# CANBed_case.net
KiCad netlist of a schematic drawn in EAGLE
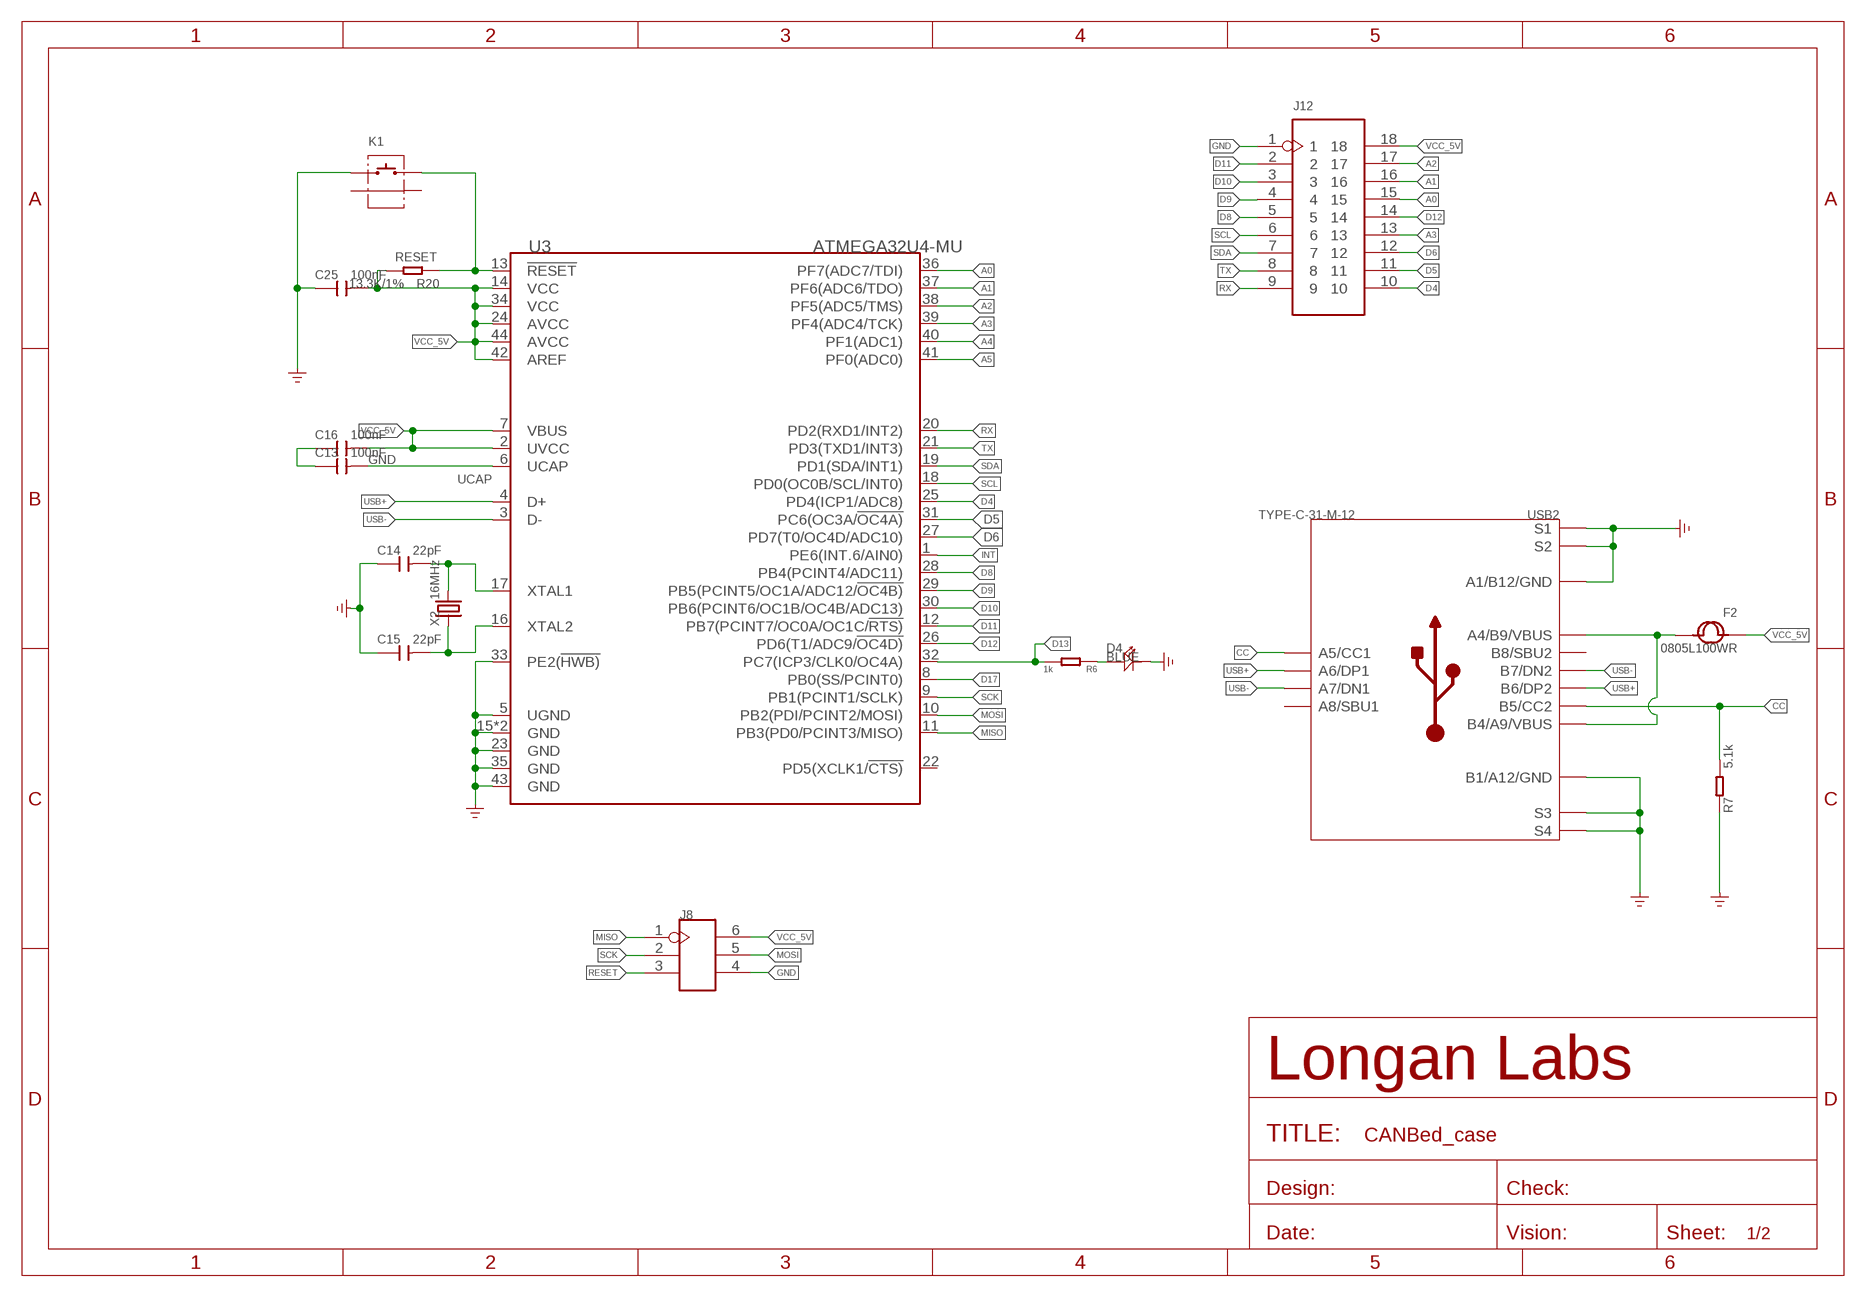
[diagram p0: schematic, sheet 1, part 1 of 2]
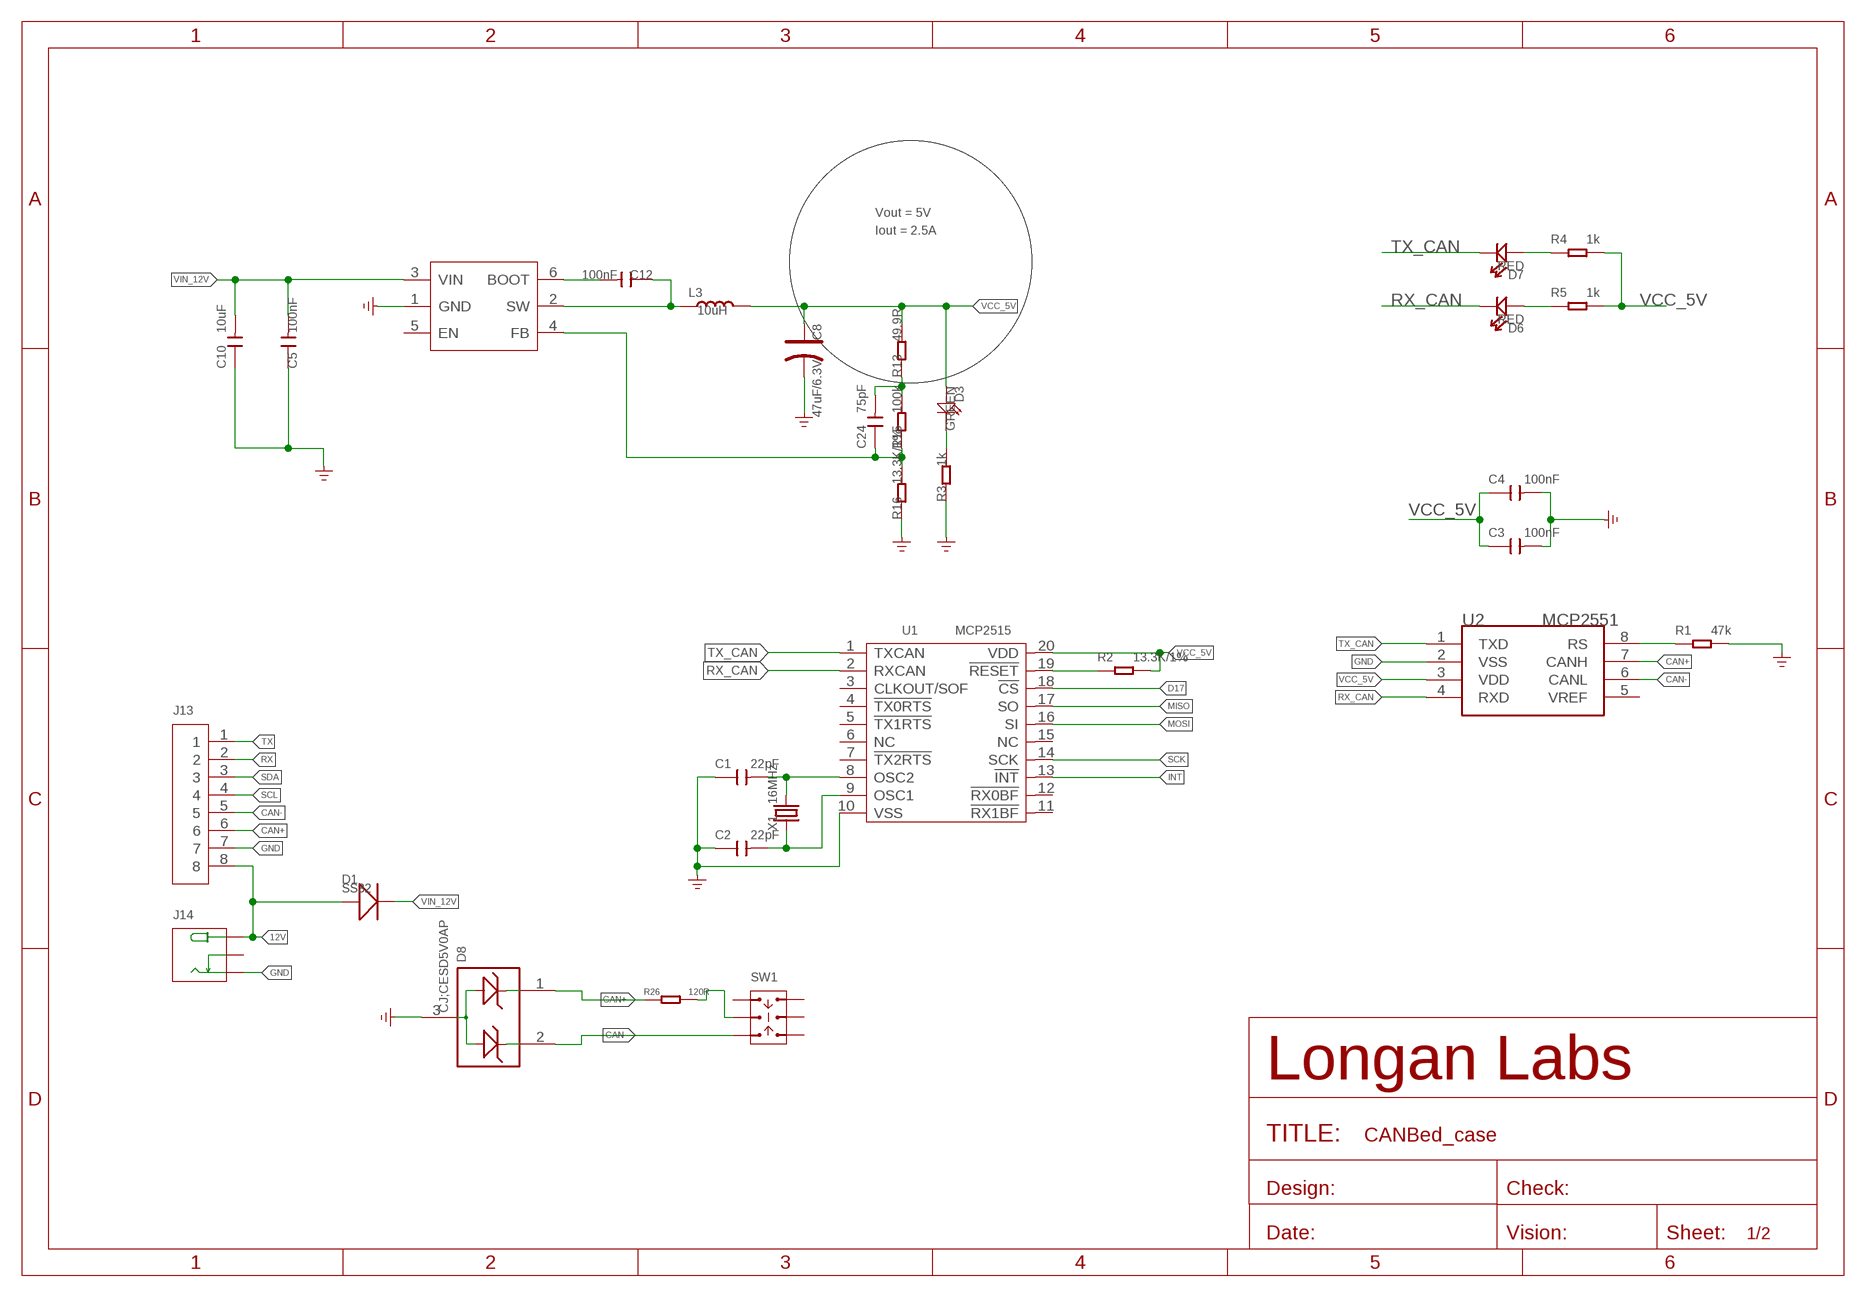
[diagram p1: schematic, sheet 1, part 2 of 2]

(export (version "E")
  (design (tool "Eeschema 10.0.6"))
  (components
    (comp (ref "C1")
      (value "22pF")
      (footprint "eagle-import:C0603")
      (libsource (lib "eagle-import") (part "CAP-0603"))
    )
    (comp (ref "C2")
      (value "22pF")
      (footprint "eagle-import:C0603")
      (libsource (lib "eagle-import") (part "CAP-0603"))
    )
    (comp (ref "C3")
      (value "100nF")
      (footprint "eagle-import:C0603")
      (libsource (lib "eagle-import") (part "CAP-0603"))
    )
    (comp (ref "C4")
      (value "100nF")
      (footprint "eagle-import:C0603")
      (libsource (lib "eagle-import") (part "CAP-0603"))
    )
    (comp (ref "C5")
      (value "100nF")
      (footprint "eagle-import:C0603")
      (libsource (lib "eagle-import") (part "CAP-0603"))
    )
    (comp (ref "C8")
      (value "47uF/6.3V")
      (footprint "eagle-import:AVX-B")
      (libsource (lib "eagle-import") (part "CAP-POLAR-AVX-B"))
    )
    (comp (ref "C10")
      (value "10uF")
      (footprint "eagle-import:C1206")
      (libsource (lib "eagle-import") (part "CAP-1206"))
    )
    (comp (ref "C12")
      (value "100nF")
      (footprint "eagle-import:C0603")
      (libsource (lib "eagle-import") (part "CAP-0603"))
    )
    (comp (ref "C13")
      (value "100nF")
      (footprint "eagle-import:C0603")
      (libsource (lib "eagle-import") (part "CAP-0603"))
    )
    (comp (ref "C14")
      (value "22pF")
      (footprint "eagle-import:C0603")
      (libsource (lib "eagle-import") (part "CAP-0603"))
    )
    (comp (ref "C15")
      (value "22pF")
      (footprint "eagle-import:C0603")
      (libsource (lib "eagle-import") (part "CAP-0603"))
    )
    (comp (ref "C16")
      (value "100nF")
      (footprint "eagle-import:C0603")
      (libsource (lib "eagle-import") (part "CAP-0603"))
    )
    (comp (ref "C24")
      (value "75pF")
      (footprint "eagle-import:C0603")
      (libsource (lib "eagle-import") (part "CAP-0603"))
    )
    (comp (ref "C25")
      (value "100nF")
      (footprint "eagle-import:C0603")
      (libsource (lib "eagle-import") (part "CAP-0603"))
    )
    (comp (ref "D1")
      (value "SS32")
      (footprint "eagle-import:DO-214AC")
      (libsource (lib "eagle-import") (part "DIODE'SMA'"))
    )
    (comp (ref "D3")
      (value "GREEN")
      (footprint "eagle-import:LED0805-SIDE")
      (libsource (lib "eagle-import") (part "fat cong_LED'0805'"))
    )
    (comp (ref "D4")
      (value "BLUE")
      (footprint "eagle-import:LED0805-SIDE")
      (libsource (lib "eagle-import") (part "fat cong_LED'0805'"))
    )
    (comp (ref "D6")
      (value "RED")
      (footprint "eagle-import:LED-0603")
      (libsource (lib "eagle-import") (part "LED'0603'"))
    )
    (comp (ref "D7")
      (value "RED")
      (footprint "eagle-import:LED-0603")
      (libsource (lib "eagle-import") (part "LED'0603'"))
    )
    (comp (ref "D8")
      (value "CJ;CESD5V0AP")
      (footprint "eagle-import:SOT-23")
      (libsource (lib "eagle-import") (part "D-ESD-3P'CESD3V3AP'"))
    )
    (comp (ref "F2")
      (value "0805L100WR")
      (footprint "eagle-import:F0805")
      (libsource (lib "eagle-import") (part "FUSE0805"))
    )
    (comp (ref "J8")
      (value "HEADER-2X3P-2.54")
      (footprint "eagle-import:H2X3-2.54")
      (libsource (lib "eagle-import") (part "HEADER-2X3P-2.54"))
    )
    (comp (ref "J12")
      (value "HEADER-2X9P-2.54")
      (footprint "eagle-import:H2X9-2.54")
      (libsource (lib "eagle-import") (part "HEADER-2X9P-2.54"))
    )
    (comp (ref "J13")
      (value "TERMINAL-8P")
      (footprint "eagle-import:TERMINAL8P-5.0-41.2X12.2X7.8MM")
      (libsource (lib "eagle-import") (part "TERMINAL-8P"))
    )
    (comp (ref "J14")
      (value "POWER-JACK-DC-320120003")
      (footprint "eagle-import:DCJ3P-14.2X11.0X9.0MM")
      (libsource (lib "eagle-import") (part "POWER-JACK-DC-320120003"))
    )
    (comp (ref "K1")
      (value "BUTTON-2+2P-K2-1102AQ")
      (footprint "eagle-import:SW4-4.5-7X6.8X6MM")
      (libsource (lib "eagle-import") (part "BUTTON-2+2P-K2-1102AQ"))
    )
    (comp (ref "L3")
      (value "10uH")
      (footprint "eagle-import:INT2-SMD-6.6X7.1X3MM")
      (libsource (lib "eagle-import") (part "INDUCTOR-6.6X7.1"))
    )
    (comp (ref "R1")
      (value "47k")
      (footprint "eagle-import:R0603")
      (libsource (lib "eagle-import") (part "RES-0603"))
    )
    (comp (ref "R2")
      (value "13.3K/1%")
      (footprint "eagle-import:R0603")
      (libsource (lib "eagle-import") (part "RES-0603"))
    )
    (comp (ref "R3")
      (value "1k")
      (footprint "eagle-import:R0603")
      (libsource (lib "eagle-import") (part "RES-0603"))
    )
    (comp (ref "R4")
      (value "1k")
      (footprint "eagle-import:R0603")
      (libsource (lib "eagle-import") (part "RES-0603"))
    )
    (comp (ref "R5")
      (value "1k")
      (footprint "eagle-import:R0603")
      (libsource (lib "eagle-import") (part "RES-0603"))
    )
    (comp (ref "R6")
      (value "1k")
      (footprint "eagle-import:R0603")
      (libsource (lib "eagle-import") (part "RES-0603"))
    )
    (comp (ref "R7")
      (value "5.1k")
      (footprint "eagle-import:R0603")
      (libsource (lib "eagle-import") (part "RES-0603"))
    )
    (comp (ref "R13")
      (value "49.9R")
      (footprint "eagle-import:R0603")
      (libsource (lib "eagle-import") (part "RES-0603"))
    )
    (comp (ref "R15")
      (value "100k")
      (footprint "eagle-import:R0603")
      (libsource (lib "eagle-import") (part "RES-0603"))
    )
    (comp (ref "R16")
      (value "13.3K/1%")
      (footprint "eagle-import:R0603")
      (libsource (lib "eagle-import") (part "RES-0603"))
    )
    (comp (ref "R20")
      (value "13.3K/1%")
      (footprint "eagle-import:R0603")
      (libsource (lib "eagle-import") (part "RES-0603"))
    )
    (comp (ref "R26")
      (value "120R")
      (footprint "eagle-import:R0603")
      (libsource (lib "eagle-import") (part "RES-0603"))
    )
    (comp (ref "SW1")
      (value "SWITCH-2CH-6P-311010004")
      (footprint "eagle-import:SW6-2.54-9.0X3.5X3.2+2.0MM")
      (libsource (lib "eagle-import") (part "SWITCH-2CH-6P-311010004"))
    )
    (comp (ref "U1")
      (value "MCP2515")
      (footprint "eagle-import:TSSOP20-0.65-6.5X4.4MM")
      (libsource (lib "eagle-import") (part "MCP2515'ST'"))
    )
    (comp (ref "U2")
      (value "MCP2551")
      (footprint "eagle-import:SOIC8-6.0")
      (libsource (lib "eagle-import") (part "MCP2551-SOIC8"))
    )
    (comp (ref "U3")
      (value "ATMEGA32U4-MU")
      (footprint "eagle-import:QFN44G-0.5-7X7MM")
      (libsource (lib "eagle-import") (part "MCU-ATMEGA32U4-MUR"))
    )
    (comp (ref "U6")
      (value "PMIC-TPS54302")
      (footprint "eagle-import:SOT-23-6")
      (libsource (lib "eagle-import") (part "PMIC-TPS54302"))
    )
    (comp (ref "USB2")
      (value "TYPE-C-31-M-12")
      (footprint "eagle-import:USB2.0-TYPE-C")
      (libsource (lib "eagle-import") (part "USB2.0-TYPE-C"))
    )
    (comp (ref "X1")
      (value "16MHz")
      (footprint "eagle-import:X4-SMD-3.2X2.5X0.7MM")
      (libsource (lib "eagle-import") (part "CRYSTAL-2P-3225"))
    )
    (comp (ref "X2")
      (value "16MHz")
      (footprint "eagle-import:X4-SMD-3.2X2.5X0.7MM")
      (libsource (lib "eagle-import") (part "CRYSTAL-2P-3225"))
    )
  )
  (nets
    (net (code "1") (name "12V") (class "Default")
      (node (ref "D1") (pin "1") (pinfunction "+_1") (pintype "passive"))
      (node (ref "J13") (pin "8") (pinfunction "8_8") (pintype "bidirectional"))
      (node (ref "J14") (pin "+") (pinfunction "+_+") (pintype "bidirectional"))
    )
    (net (code "2") (name "A0") (class "Default")
      (node (ref "J12") (pin "15") (pinfunction "15_15") (pintype "bidirectional"))
      (node (ref "U3") (pin "36") (pinfunction "PF7(ADC7/TDI)_36") (pintype "bidirectional"))
    )
    (net (code "3") (name "A1") (class "Default")
      (node (ref "J12") (pin "16") (pinfunction "16_16") (pintype "bidirectional"))
      (node (ref "U3") (pin "37") (pinfunction "PF6(ADC6/TDO)_37") (pintype "bidirectional"))
    )
    (net (code "4") (name "A2") (class "Default")
      (node (ref "J12") (pin "17") (pinfunction "17_17") (pintype "bidirectional"))
      (node (ref "U3") (pin "38") (pinfunction "PF5(ADC5/TMS)_38") (pintype "bidirectional"))
    )
    (net (code "5") (name "A3") (class "Default")
      (node (ref "J12") (pin "13") (pinfunction "13_13") (pintype "bidirectional"))
      (node (ref "U3") (pin "39") (pinfunction "PF4(ADC4/TCK)_39") (pintype "bidirectional"))
    )
    (net (code "6") (name "A4") (class "Default")
      (node (ref "U3") (pin "40") (pinfunction "PF1(ADC1)_40") (pintype "bidirectional"))
    )
    (net (code "7") (name "A5") (class "Default")
      (node (ref "U3") (pin "41") (pinfunction "PF0(ADC0)_41") (pintype "bidirectional"))
    )
    (net (code "8") (name "CAN+") (class "Default")
      (node (ref "D8") (pin "1") (pinfunction "1_1") (pintype "bidirectional"))
      (node (ref "J13") (pin "6") (pinfunction "6_6") (pintype "bidirectional"))
      (node (ref "R26") (pin "1") (pinfunction "1_1") (pintype "passive"))
      (node (ref "U2") (pin "7") (pinfunction "CANH_7") (pintype "bidirectional"))
    )
    (net (code "9") (name "CAN-") (class "Default")
      (node (ref "D8") (pin "2") (pinfunction "2_2") (pintype "bidirectional"))
      (node (ref "J13") (pin "5") (pinfunction "5_5") (pintype "bidirectional"))
      (node (ref "SW1") (pin "CH1B") (pinfunction "CH1B_CH1B") (pintype "bidirectional"))
      (node (ref "U2") (pin "6") (pinfunction "CANL_6") (pintype "bidirectional"))
    )
    (net (code "10") (name "CC") (class "Default")
      (node (ref "R7") (pin "2") (pinfunction "2_2") (pintype "passive"))
      (node (ref "USB2") (pin "A5") (pinfunction "A5/CC1_A5") (pintype "bidirectional"))
      (node (ref "USB2") (pin "B5") (pinfunction "B5/CC2_B5") (pintype "bidirectional"))
    )
    (net (code "11") (name "D4") (class "Default")
      (node (ref "J12") (pin "10") (pinfunction "10_10") (pintype "bidirectional"))
      (node (ref "U3") (pin "25") (pinfunction "PD4(ICP1/ADC8)_25") (pintype "bidirectional"))
    )
    (net (code "12") (name "D5") (class "Default")
      (node (ref "J12") (pin "11") (pinfunction "11_11") (pintype "bidirectional"))
      (node (ref "U3") (pin "31") (pinfunction "PC6(OC3A/~{OC4A})_31") (pintype "bidirectional"))
    )
    (net (code "13") (name "D6") (class "Default")
      (node (ref "J12") (pin "12") (pinfunction "12_12") (pintype "bidirectional"))
      (node (ref "U3") (pin "27") (pinfunction "PD7(T0/OC4D/ADC10)_27") (pintype "bidirectional"))
    )
    (net (code "14") (name "D8") (class "Default")
      (node (ref "J12") (pin "5") (pinfunction "5_5") (pintype "bidirectional"))
      (node (ref "U3") (pin "28") (pinfunction "PB4(PCINT4/ADC11)_28") (pintype "bidirectional"))
    )
    (net (code "15") (name "D9") (class "Default")
      (node (ref "J12") (pin "4") (pinfunction "4_4") (pintype "bidirectional"))
      (node (ref "U3") (pin "29") (pinfunction "PB5(PCINT5/OC1A/ADC12/~{OC4B})_29") (pintype "bidirectional"))
    )
    (net (code "16") (name "D10") (class "Default")
      (node (ref "J12") (pin "3") (pinfunction "3_3") (pintype "bidirectional"))
      (node (ref "U3") (pin "30") (pinfunction "PB6(PCINT6/OC1B/OC4B/ADC13)_30") (pintype "bidirectional"))
    )
    (net (code "17") (name "D11") (class "Default")
      (node (ref "J12") (pin "2") (pinfunction "2_2") (pintype "bidirectional"))
      (node (ref "U3") (pin "12") (pinfunction "PB7(PCINT7/OC0A/OC1C/~{RTS})_12") (pintype "bidirectional"))
    )
    (net (code "18") (name "D12") (class "Default")
      (node (ref "J12") (pin "14") (pinfunction "14_14") (pintype "bidirectional"))
      (node (ref "U3") (pin "26") (pinfunction "PD6(T1/ADC9/~{OC4D})_26") (pintype "bidirectional"))
    )
    (net (code "19") (name "D13") (class "Default")
      (node (ref "R6") (pin "2") (pinfunction "2_2") (pintype "passive"))
      (node (ref "U3") (pin "32") (pinfunction "PC7(ICP3/CLK0/OC4A)_32") (pintype "bidirectional"))
    )
    (net (code "20") (name "D17") (class "Default")
      (node (ref "U1") (pin "18") (pinfunction "~{CS}_18") (pintype "bidirectional"))
      (node (ref "U3") (pin "8") (pinfunction "PB0(SS/PCINT0)_8") (pintype "bidirectional"))
    )
    (net (code "21") (name "GND") (class "Default")
      (node (ref "C1") (pin "1") (pinfunction "1_1") (pintype "passive"))
      (node (ref "C10") (pin "1") (pinfunction "1_1") (pintype "passive"))
      (node (ref "C13") (pin "1") (pinfunction "1_1") (pintype "passive"))
      (node (ref "C14") (pin "1") (pinfunction "1_1") (pintype "passive"))
      (node (ref "C15") (pin "1") (pinfunction "1_1") (pintype "passive"))
      (node (ref "C16") (pin "1") (pinfunction "1_1") (pintype "passive"))
      (node (ref "C2") (pin "1") (pinfunction "1_1") (pintype "passive"))
      (node (ref "C25") (pin "1") (pinfunction "1_1") (pintype "passive"))
      (node (ref "C3") (pin "2") (pinfunction "2_2") (pintype "passive"))
      (node (ref "C4") (pin "2") (pinfunction "2_2") (pintype "passive"))
      (node (ref "C5") (pin "1") (pinfunction "1_1") (pintype "passive"))
      (node (ref "C8") (pin "-") (pinfunction "-_-") (pintype "passive"))
      (node (ref "D4") (pin "-") (pinfunction "-_-") (pintype "passive"))
      (node (ref "D8") (pin "3") (pinfunction "3_3") (pintype "bidirectional"))
      (node (ref "J12") (pin "1") (pinfunction "1_1") (pintype "bidirectional"))
      (node (ref "J13") (pin "7") (pinfunction "7_7") (pintype "bidirectional"))
      (node (ref "J14") (pin "-1") (pinfunction "-_-1") (pintype "bidirectional"))
      (node (ref "J8") (pin "4") (pinfunction "4_4") (pintype "bidirectional"))
      (node (ref "K1") (pin "1") (pinfunction "1_1") (pintype "bidirectional"))
      (node (ref "R1") (pin "2") (pinfunction "2_2") (pintype "passive"))
      (node (ref "R16") (pin "1") (pinfunction "1_1") (pintype "passive"))
      (node (ref "R3") (pin "1") (pinfunction "1_1") (pintype "passive"))
      (node (ref "R7") (pin "1") (pinfunction "1_1") (pintype "passive"))
      (node (ref "U1") (pin "10") (pinfunction "VSS_10") (pintype "bidirectional"))
      (node (ref "U2") (pin "2") (pinfunction "VSS_2") (pintype "bidirectional"))
      (node (ref "U3") (pin "15") (pinfunction "GND_15") (pintype "bidirectional"))
      (node (ref "U3") (pin "23") (pinfunction "GND_23") (pintype "bidirectional"))
      (node (ref "U3") (pin "33") (pinfunction "PE2(~{HWB})_33") (pintype "bidirectional"))
      (node (ref "U3") (pin "35") (pinfunction "GND_35") (pintype "bidirectional"))
      (node (ref "U3") (pin "43") (pinfunction "GND_43") (pintype "bidirectional"))
      (node (ref "U3") (pin "5") (pinfunction "UGND_5") (pintype "bidirectional"))
      (node (ref "U3") (pin "TAB") (pinfunction "GND_TAB") (pintype "bidirectional"))
      (node (ref "U6") (pin "1") (pinfunction "GND_1") (pintype "bidirectional"))
      (node (ref "USB2") (pin "A1_B12") (pinfunction "A1/B12/GND_A1_B12") (pintype "bidirectional"))
      (node (ref "USB2") (pin "B1_A12") (pinfunction "B1/A12/GND_B1_A12") (pintype "bidirectional"))
      (node (ref "USB2") (pin "S1") (pinfunction "S1_S1") (pintype "bidirectional"))
      (node (ref "USB2") (pin "S2") (pinfunction "S2_S2") (pintype "bidirectional"))
      (node (ref "USB2") (pin "S3") (pinfunction "S3_S3") (pintype "bidirectional"))
      (node (ref "USB2") (pin "S4") (pinfunction "S4_S4") (pintype "bidirectional"))
      (node (ref "USB2") (pin "S5") (pinfunction "S1_S5") (pintype "bidirectional"))
      (node (ref "USB2") (pin "S6") (pinfunction "S2_S6") (pintype "bidirectional"))
    )
    (net (code "22") (name "INT") (class "Default")
      (node (ref "U1") (pin "13") (pinfunction "~{INT}_13") (pintype "bidirectional"))
      (node (ref "U3") (pin "1") (pinfunction "PE6(INT.6/AIN0)_1") (pintype "bidirectional"))
    )
    (net (code "23") (name "MISO") (class "Default")
      (node (ref "J8") (pin "1") (pinfunction "1_1") (pintype "bidirectional"))
      (node (ref "U1") (pin "17") (pinfunction "SO_17") (pintype "bidirectional"))
      (node (ref "U3") (pin "11") (pinfunction "PB3(PD0/PCINT3/MISO)_11") (pintype "bidirectional"))
    )
    (net (code "24") (name "MOSI") (class "Default")
      (node (ref "J8") (pin "5") (pinfunction "5_5") (pintype "bidirectional"))
      (node (ref "U1") (pin "16") (pinfunction "SI_16") (pintype "bidirectional"))
      (node (ref "U3") (pin "10") (pinfunction "PB2(PDI/PCINT2/MOSI)_10") (pintype "bidirectional"))
    )
    (net (code "25") (name "Net-(C24-Pad2)") (class "Default")
      (node (ref "C24") (pin "2") (pinfunction "2_2") (pintype "passive"))
      (node (ref "R13") (pin "1") (pinfunction "1_1") (pintype "passive"))
      (node (ref "R15") (pin "2") (pinfunction "2_2") (pintype "passive"))
    )
    (net (code "26") (name "Net-(D3-Pad-)") (class "Default")
      (node (ref "D3") (pin "-") (pinfunction "-_-") (pintype "passive"))
      (node (ref "R3") (pin "2") (pinfunction "2_2") (pintype "passive"))
    )
    (net (code "27") (name "Net-(D4-Pad+)") (class "Default")
      (node (ref "D4") (pin "+") (pinfunction "+_+") (pintype "passive"))
      (node (ref "R6") (pin "1") (pinfunction "1_1") (pintype "passive"))
    )
    (net (code "28") (name "Net-(D6-Pad+)") (class "Default")
      (node (ref "D6") (pin "+") (pinfunction "+_+") (pintype "passive"))
      (node (ref "R5") (pin "1") (pinfunction "1_1") (pintype "passive"))
    )
    (net (code "29") (name "Net-(D7-Pad+)") (class "Default")
      (node (ref "D7") (pin "+") (pinfunction "+_+") (pintype "passive"))
      (node (ref "R4") (pin "1") (pinfunction "1_1") (pintype "passive"))
    )
    (net (code "30") (name "Net-(R26-Pad2)") (class "Default")
      (node (ref "R26") (pin "2") (pinfunction "2_2") (pintype "passive"))
      (node (ref "SW1") (pin "COM1") (pinfunction "COM1_COM1") (pintype "bidirectional"))
    )
    (net (code "31") (name "Net-(U1-OSC1)") (class "Default")
      (node (ref "C2") (pin "2") (pinfunction "2_2") (pintype "passive"))
      (node (ref "U1") (pin "9") (pinfunction "OSC1_9") (pintype "bidirectional"))
      (node (ref "X1") (pin "1") (pinfunction "1_1") (pintype "passive"))
    )
    (net (code "32") (name "Net-(U1-OSC2)") (class "Default")
      (node (ref "C1") (pin "2") (pinfunction "2_2") (pintype "passive"))
      (node (ref "U1") (pin "8") (pinfunction "OSC2_8") (pintype "bidirectional"))
      (node (ref "X1") (pin "3") (pinfunction "2_3") (pintype "passive"))
    )
    (net (code "33") (name "Net-(U1-~{RESET})") (class "Default")
      (node (ref "R2") (pin "1") (pinfunction "1_1") (pintype "passive"))
      (node (ref "U1") (pin "19") (pinfunction "~{RESET}_19") (pintype "bidirectional"))
    )
    (net (code "34") (name "Net-(U2-RS)") (class "Default")
      (node (ref "R1") (pin "1") (pinfunction "1_1") (pintype "passive"))
      (node (ref "U2") (pin "8") (pinfunction "RS_8") (pintype "bidirectional"))
    )
    (net (code "35") (name "Net-(U3-XTAL1)") (class "Default")
      (node (ref "C14") (pin "2") (pinfunction "2_2") (pintype "passive"))
      (node (ref "U3") (pin "17") (pinfunction "XTAL1_17") (pintype "bidirectional"))
      (node (ref "X2") (pin "3") (pinfunction "2_3") (pintype "passive"))
    )
    (net (code "36") (name "Net-(U3-XTAL2)") (class "Default")
      (node (ref "C15") (pin "2") (pinfunction "2_2") (pintype "passive"))
      (node (ref "U3") (pin "16") (pinfunction "XTAL2_16") (pintype "bidirectional"))
      (node (ref "X2") (pin "1") (pinfunction "1_1") (pintype "passive"))
    )
    (net (code "37") (name "Net-(U6-BOOT)") (class "Default")
      (node (ref "C12") (pin "2") (pinfunction "2_2") (pintype "passive"))
      (node (ref "U6") (pin "6") (pinfunction "BOOT_6") (pintype "bidirectional"))
    )
    (net (code "38") (name "Net-(U6-FB)") (class "Default")
      (node (ref "C24") (pin "1") (pinfunction "1_1") (pintype "passive"))
      (node (ref "R15") (pin "1") (pinfunction "1_1") (pintype "passive"))
      (node (ref "R16") (pin "2") (pinfunction "2_2") (pintype "passive"))
      (node (ref "U6") (pin "4") (pinfunction "FB_4") (pintype "bidirectional"))
    )
    (net (code "39") (name "Net-(U6-SW)") (class "Default")
      (node (ref "C12") (pin "1") (pinfunction "1_1") (pintype "passive"))
      (node (ref "L3") (pin "1") (pinfunction "1_1") (pintype "passive"))
      (node (ref "U6") (pin "2") (pinfunction "SW_2") (pintype "bidirectional"))
    )
    (net (code "40") (name "Net-(USB2-A4{slash}B9{slash}VBUS)") (class "Default")
      (node (ref "F2") (pin "2") (pinfunction "2_2") (pintype "bidirectional"))
      (node (ref "USB2") (pin "A4_B9") (pinfunction "A4/B9/VBUS_A4_B9") (pintype "bidirectional"))
      (node (ref "USB2") (pin "B4_A9") (pinfunction "B4/A9/VBUS_B4_A9") (pintype "bidirectional"))
    )
    (net (code "41") (name "RESET") (class "Default")
      (node (ref "J8") (pin "3") (pinfunction "3_3") (pintype "bidirectional"))
      (node (ref "K1") (pin "2") (pinfunction "2_2") (pintype "bidirectional"))
      (node (ref "R20") (pin "1") (pinfunction "1_1") (pintype "passive"))
      (node (ref "U3") (pin "13") (pinfunction "~{RESET}_13") (pintype "bidirectional"))
    )
    (net (code "42") (name "RX") (class "Default")
      (node (ref "J12") (pin "9") (pinfunction "9_9") (pintype "bidirectional"))
      (node (ref "J13") (pin "2") (pinfunction "2_2") (pintype "bidirectional"))
      (node (ref "U3") (pin "20") (pinfunction "PD2(RXD1/INT2)_20") (pintype "bidirectional"))
    )
    (net (code "43") (name "RX_CAN") (class "Default")
      (node (ref "D6") (pin "-") (pinfunction "-_-") (pintype "passive"))
      (node (ref "U1") (pin "2") (pinfunction "RXCAN_2") (pintype "bidirectional"))
      (node (ref "U2") (pin "4") (pinfunction "RXD_4") (pintype "bidirectional"))
    )
    (net (code "44") (name "SCK") (class "Default")
      (node (ref "J8") (pin "2") (pinfunction "2_2") (pintype "bidirectional"))
      (node (ref "U1") (pin "14") (pinfunction "SCK_14") (pintype "bidirectional"))
      (node (ref "U3") (pin "9") (pinfunction "PB1(PCINT1/SCLK)_9") (pintype "bidirectional"))
    )
    (net (code "45") (name "SCL") (class "Default")
      (node (ref "J12") (pin "6") (pinfunction "6_6") (pintype "bidirectional"))
      (node (ref "J13") (pin "4") (pinfunction "4_4") (pintype "bidirectional"))
      (node (ref "U3") (pin "18") (pinfunction "PD0(OC0B/SCL/INT0)_18") (pintype "bidirectional"))
    )
    (net (code "46") (name "SDA") (class "Default")
      (node (ref "J12") (pin "7") (pinfunction "7_7") (pintype "bidirectional"))
      (node (ref "J13") (pin "3") (pinfunction "3_3") (pintype "bidirectional"))
      (node (ref "U3") (pin "19") (pinfunction "PD1(SDA/INT1)_19") (pintype "bidirectional"))
    )
    (net (code "47") (name "TX") (class "Default")
      (node (ref "J12") (pin "8") (pinfunction "8_8") (pintype "bidirectional"))
      (node (ref "J13") (pin "1") (pinfunction "1_1") (pintype "bidirectional"))
      (node (ref "U3") (pin "21") (pinfunction "PD3(TXD1/INT3)_21") (pintype "bidirectional"))
    )
    (net (code "48") (name "TX_CAN") (class "Default")
      (node (ref "D7") (pin "-") (pinfunction "-_-") (pintype "passive"))
      (node (ref "U1") (pin "1") (pinfunction "TXCAN_1") (pintype "bidirectional"))
      (node (ref "U2") (pin "1") (pinfunction "TXD_1") (pintype "bidirectional"))
    )
    (net (code "49") (name "UCAP") (class "Default")
      (node (ref "C13") (pin "2") (pinfunction "2_2") (pintype "passive"))
      (node (ref "U3") (pin "6") (pinfunction "UCAP_6") (pintype "bidirectional"))
    )
    (net (code "50") (name "USB+") (class "Default")
      (node (ref "U3") (pin "4") (pinfunction "D+_4") (pintype "bidirectional"))
      (node (ref "USB2") (pin "A6") (pinfunction "A6/DP1_A6") (pintype "bidirectional"))
      (node (ref "USB2") (pin "B6") (pinfunction "B6/DP2_B6") (pintype "bidirectional"))
    )
    (net (code "51") (name "USB-") (class "Default")
      (node (ref "U3") (pin "3") (pinfunction "D-_3") (pintype "bidirectional"))
      (node (ref "USB2") (pin "A7") (pinfunction "A7/DN1_A7") (pintype "bidirectional"))
      (node (ref "USB2") (pin "B7") (pinfunction "B7/DN2_B7") (pintype "bidirectional"))
    )
    (net (code "52") (name "VCC_5V") (class "Default")
      (node (ref "C16") (pin "2") (pinfunction "2_2") (pintype "passive"))
      (node (ref "C25") (pin "2") (pinfunction "2_2") (pintype "passive"))
      (node (ref "C3") (pin "1") (pinfunction "1_1") (pintype "passive"))
      (node (ref "C4") (pin "1") (pinfunction "1_1") (pintype "passive"))
      (node (ref "C8") (pin "+") (pinfunction "+_+") (pintype "passive"))
      (node (ref "D3") (pin "+") (pinfunction "+_+") (pintype "passive"))
      (node (ref "F2") (pin "1") (pinfunction "1_1") (pintype "bidirectional"))
      (node (ref "J12") (pin "18") (pinfunction "18_18") (pintype "bidirectional"))
      (node (ref "J8") (pin "6") (pinfunction "6_6") (pintype "bidirectional"))
      (node (ref "L3") (pin "2") (pinfunction "2_2") (pintype "passive"))
      (node (ref "R13") (pin "2") (pinfunction "2_2") (pintype "passive"))
      (node (ref "R2") (pin "2") (pinfunction "2_2") (pintype "passive"))
      (node (ref "R20") (pin "2") (pinfunction "2_2") (pintype "passive"))
      (node (ref "R4") (pin "2") (pinfunction "2_2") (pintype "passive"))
      (node (ref "R5") (pin "2") (pinfunction "2_2") (pintype "passive"))
      (node (ref "U1") (pin "20") (pinfunction "VDD_20") (pintype "bidirectional"))
      (node (ref "U2") (pin "3") (pinfunction "VDD_3") (pintype "bidirectional"))
      (node (ref "U3") (pin "14") (pinfunction "VCC_14") (pintype "bidirectional"))
      (node (ref "U3") (pin "2") (pinfunction "UVCC_2") (pintype "bidirectional"))
      (node (ref "U3") (pin "24") (pinfunction "AVCC_24") (pintype "bidirectional"))
      (node (ref "U3") (pin "34") (pinfunction "VCC_34") (pintype "bidirectional"))
      (node (ref "U3") (pin "42") (pinfunction "AREF_42") (pintype "bidirectional"))
      (node (ref "U3") (pin "44") (pinfunction "AVCC_44") (pintype "bidirectional"))
      (node (ref "U3") (pin "7") (pinfunction "VBUS_7") (pintype "bidirectional"))
    )
    (net (code "53") (name "VIN_12V") (class "Default")
      (node (ref "C10") (pin "2") (pinfunction "2_2") (pintype "passive"))
      (node (ref "C5") (pin "2") (pinfunction "2_2") (pintype "passive"))
      (node (ref "D1") (pin "2") (pinfunction "-_2") (pintype "passive"))
      (node (ref "U6") (pin "3") (pinfunction "VIN_3") (pintype "bidirectional"))
    )
    (net (code "54") (name "unconnected-(J14-CDN-Pad-2)") (class "Default")
      (node (ref "J14") (pin "-2") (pinfunction "CDN_-2") (pintype "bidirectional"))
    )
    (net (code "55") (name "unconnected-(K1-S1-Pad3)") (class "Default")
      (node (ref "K1") (pin "3") (pinfunction "S1_3") (pintype "bidirectional"))
    )
    (net (code "56") (name "unconnected-(K1-S2-Pad4)") (class "Default")
      (node (ref "K1") (pin "4") (pinfunction "S2_4") (pintype "bidirectional"))
    )
    (net (code "57") (name "unconnected-(SW1-PadCH1A)") (class "Default")
      (node (ref "SW1") (pin "CH1A") (pinfunction "CH1A_CH1A") (pintype "bidirectional"))
    )
    (net (code "58") (name "unconnected-(SW1-PadCH2A)") (class "Default")
      (node (ref "SW1") (pin "CH2A") (pinfunction "CH2A_CH2A") (pintype "bidirectional"))
    )
    (net (code "59") (name "unconnected-(SW1-PadCH2B)") (class "Default")
      (node (ref "SW1") (pin "CH2B") (pinfunction "CH2B_CH2B") (pintype "bidirectional"))
    )
    (net (code "60") (name "unconnected-(SW1-PadCOM2)") (class "Default")
      (node (ref "SW1") (pin "COM2") (pinfunction "COM2_COM2") (pintype "bidirectional"))
    )
    (net (code "61") (name "unconnected-(U1-CLKOUT{slash}SOF-Pad3)") (class "Default")
      (node (ref "U1") (pin "3") (pinfunction "CLKOUT/SOF_3") (pintype "bidirectional"))
    )
    (net (code "62") (name "unconnected-(U1-NC-Pad6)") (class "Default")
      (node (ref "U1") (pin "6") (pinfunction "NC_6") (pintype "bidirectional"))
    )
    (net (code "63") (name "unconnected-(U1-NC-Pad15)") (class "Default")
      (node (ref "U1") (pin "15") (pinfunction "NC_15") (pintype "bidirectional"))
    )
    (net (code "64") (name "unconnected-(U1-~{RX0BF}-Pad12)") (class "Default")
      (node (ref "U1") (pin "12") (pinfunction "~{RX0BF}_12") (pintype "bidirectional"))
    )
    (net (code "65") (name "unconnected-(U1-~{RX1BF}-Pad11)") (class "Default")
      (node (ref "U1") (pin "11") (pinfunction "~{RX1BF}_11") (pintype "bidirectional"))
    )
    (net (code "66") (name "unconnected-(U1-~{TX0RTS}-Pad4)") (class "Default")
      (node (ref "U1") (pin "4") (pinfunction "~{TX0RTS}_4") (pintype "bidirectional"))
    )
    (net (code "67") (name "unconnected-(U1-~{TX1RTS}-Pad5)") (class "Default")
      (node (ref "U1") (pin "5") (pinfunction "~{TX1RTS}_5") (pintype "bidirectional"))
    )
    (net (code "68") (name "unconnected-(U1-~{TX2RTS}-Pad7)") (class "Default")
      (node (ref "U1") (pin "7") (pinfunction "~{TX2RTS}_7") (pintype "bidirectional"))
    )
    (net (code "69") (name "unconnected-(U2-VREF-Pad5)") (class "Default")
      (node (ref "U2") (pin "5") (pinfunction "VREF_5") (pintype "bidirectional"))
    )
    (net (code "70") (name "unconnected-(U3-PD5(XCLK1{slash}~{CTS})-Pad22)") (class "Default")
      (node (ref "U3") (pin "22") (pinfunction "PD5(XCLK1/~{CTS})_22") (pintype "bidirectional"))
    )
    (net (code "71") (name "unconnected-(U6-EN-Pad5)") (class "Default")
      (node (ref "U6") (pin "5") (pinfunction "EN_5") (pintype "bidirectional"))
    )
    (net (code "72") (name "unconnected-(USB2-A8{slash}SBU1-PadA8)") (class "Default")
      (node (ref "USB2") (pin "A8") (pinfunction "A8/SBU1_A8") (pintype "bidirectional"))
    )
    (net (code "73") (name "unconnected-(USB2-B8{slash}SBU2-PadB8)") (class "Default")
      (node (ref "USB2") (pin "B8") (pinfunction "B8/SBU2_B8") (pintype "bidirectional"))
    )
  )
)
